# TIDA-010967_xWRL6432_Chip.net
KiCad netlist of a schematic drawn in Altium Designer
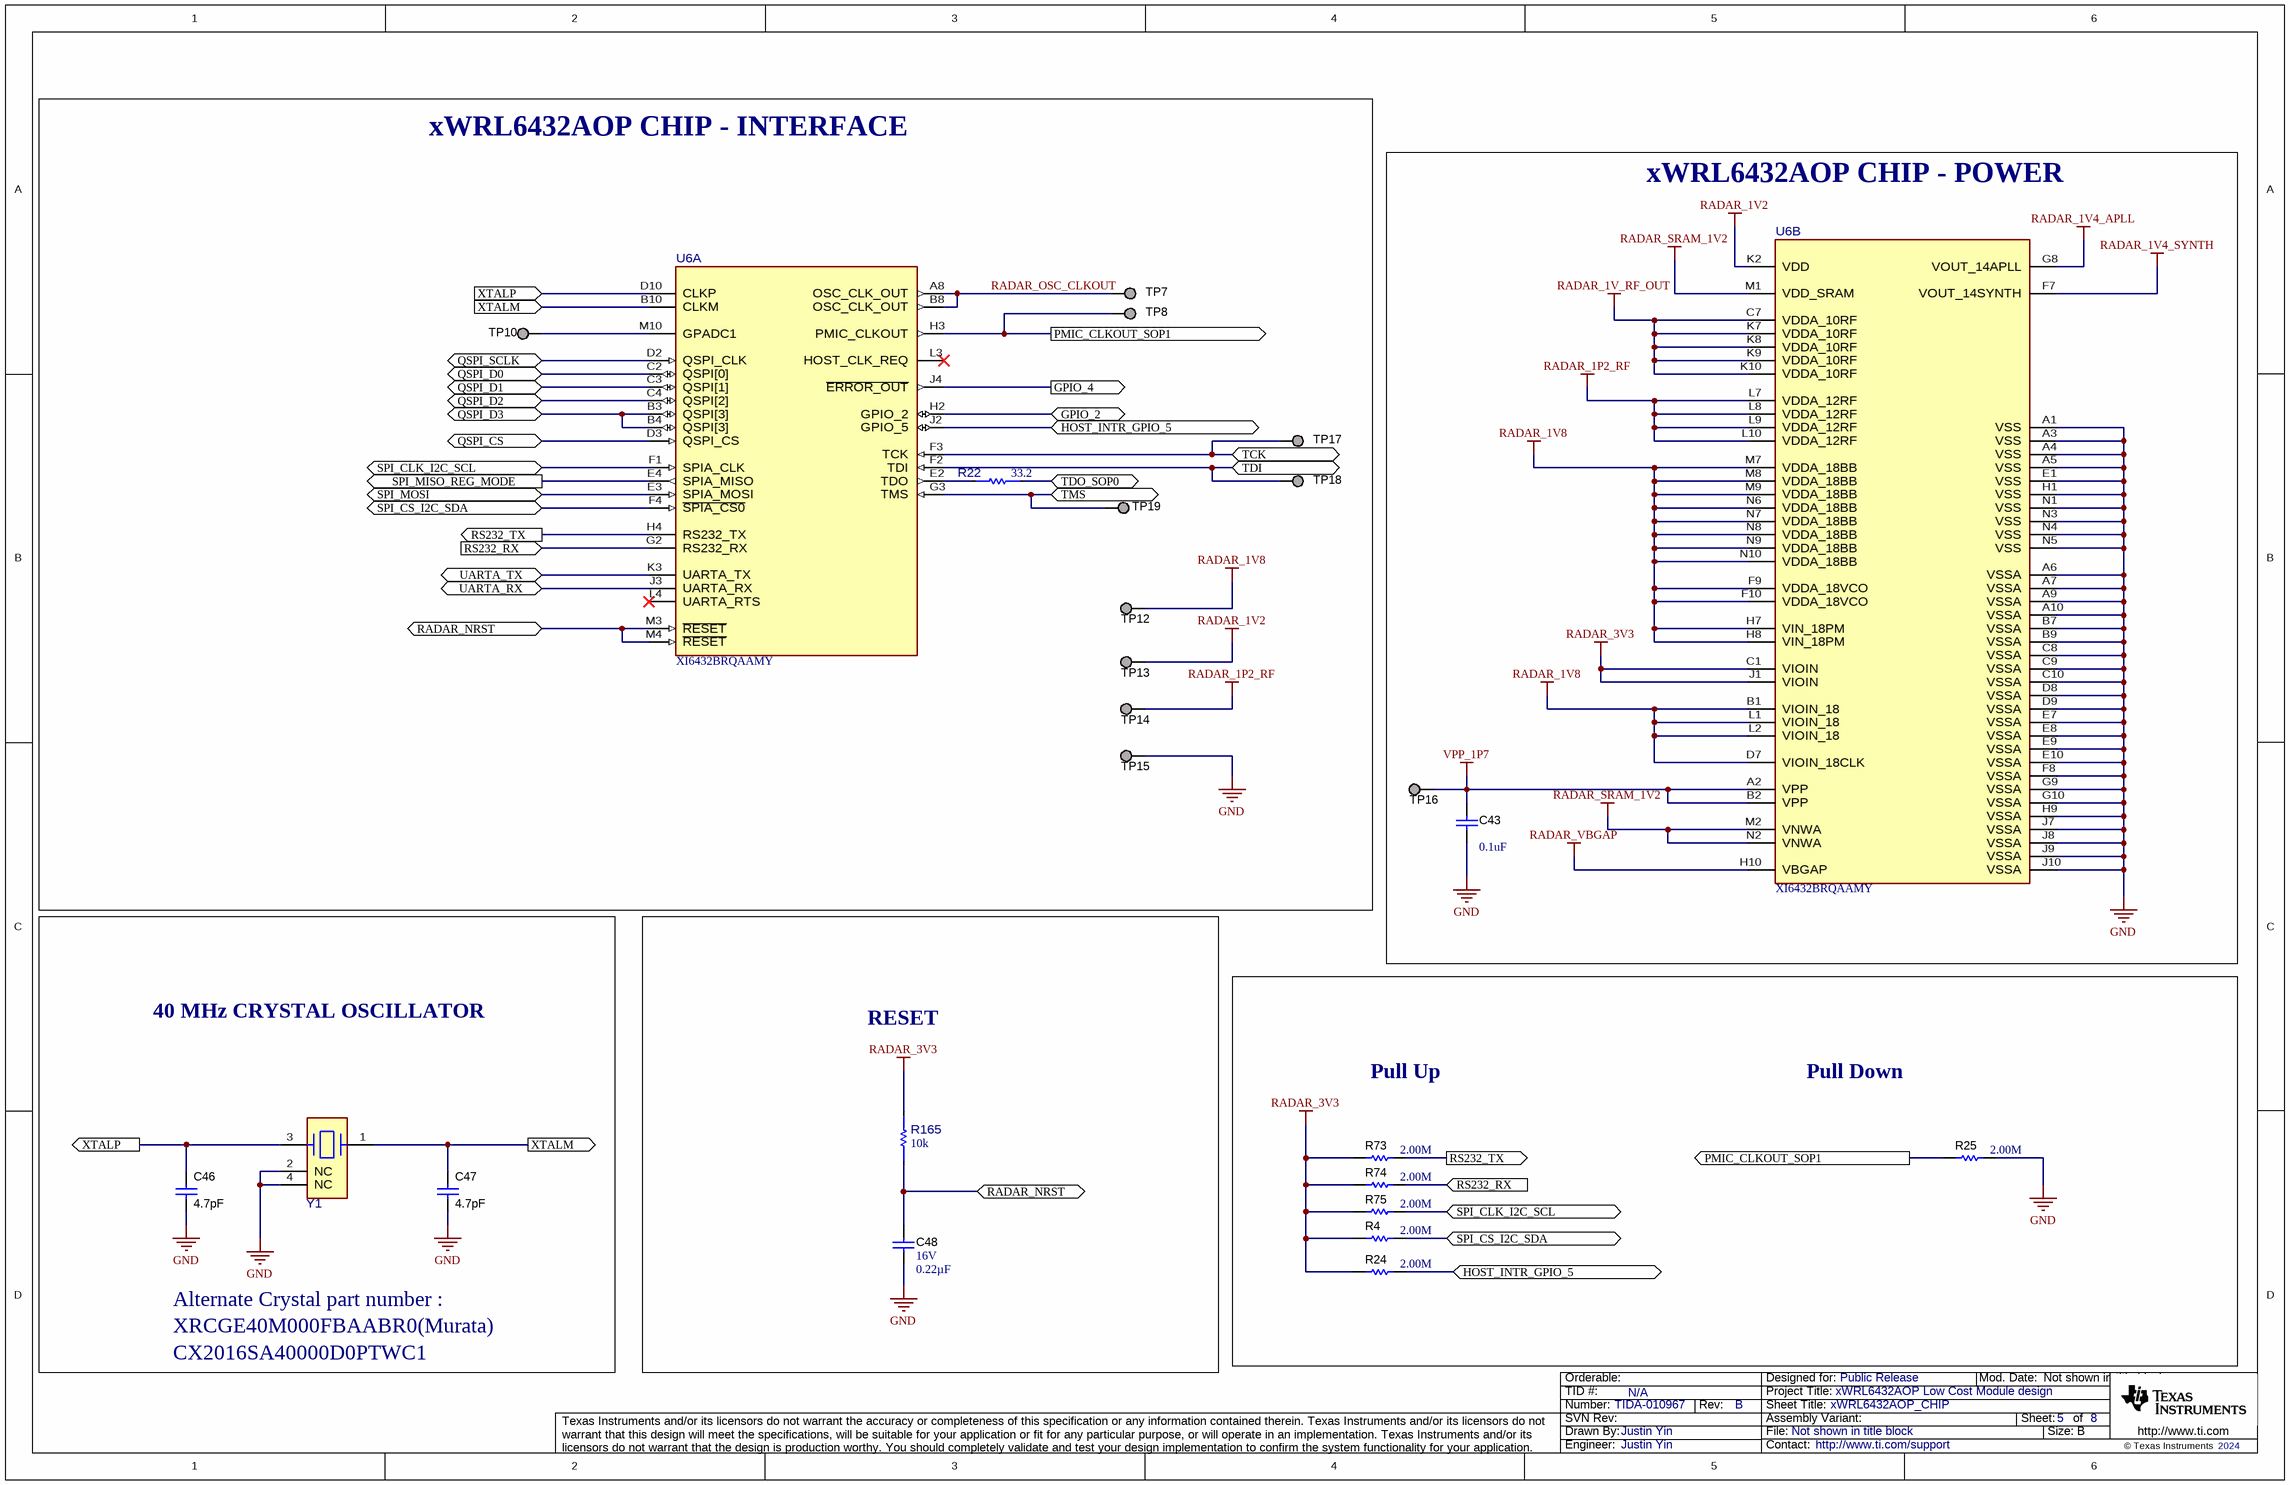
[diagram p0: TIDA-010967_xWRL6432_Chip.SchDoc]

(export (version "E")
  (design (tool "Eeschema 10.0.6"))
  (components
    (comp (ref "C43")
      (value "C1005X7R1H104K050BE")
      (footprint "0402")
      (description "CAP, CERM, 0.1 uF, 50 V,+/- 10%, X7R, 0402")
      (fields
        (field (name "MANUFACTURER") "TDK")
        (field (name "VALUEDISPLAYED") "0.1uF")
        (field (name "PUBLISHER") "Texas Instruments")
      )
      (libsource (lib "Altium Vault - TI") (part "Capacitor"))
    )
    (comp (ref "C46")
      (value "GJM1555C1H4R7BB01D")
      (footprint "0402L")
      (description "CAP, CERM, 4.7 pF, 50 V, +/- 2%, C0G/NP0, 0402")
      (fields
        (field (name "MANUFACTURER") "MuRata")
        (field (name "VALUEDISPLAYED") "4.7pF")
        (field (name "PUBLISHER") "Texas Instruments")
      )
      (libsource (lib "Altium Vault - TI") (part "CMP-0006367-2"))
    )
    (comp (ref "C47")
      (value "GJM1555C1H4R7BB01D")
      (footprint "0402L")
      (description "CAP, CERM, 4.7 pF, 50 V, +/- 2%, C0G/NP0, 0402")
      (fields
        (field (name "MANUFACTURER") "MuRata")
        (field (name "VALUEDISPLAYED") "4.7pF")
        (field (name "PUBLISHER") "Texas Instruments")
      )
      (libsource (lib "Altium Vault - TI") (part "CMP-0006367-2"))
    )
    (comp (ref "C48")
      (value "CL05B224KO5NNNC")
      (footprint "0402L")
      (description "CAP, CERM, 0.22 µF, 16 V,+/- 10%, X7R, 0402")
      (fields
        (field (name "MANUFACTURER") "Samsung Electro-Mechanics")
        (field (name "VDC_V") "16V")
        (field (name "VALUEDISPLAYED") "0.22µF")
      )
      (libsource (lib "Altium Vault - TI") (part "Capacitor"))
    )
    (comp (ref "R4")
      (value "CRCW04022M00FKED")
      (footprint "0402")
      (description "RES, 2.00 M, 1%, 0.063 W, AEC-Q200 Grade 0, 0402")
      (fields (field (name "MANUFACTURER") "Vishay-Dale") (field (name "VALUEDISPLAYED") "2.00M"))
      (libsource (lib "Altium Vault - TI") (part "Resistor"))
    )
    (comp (ref "R22")
      (value "33.2")
      (footprint "FP-RT0402FRE0733R2L_0402-MFG")
      (description "33.2 Ohms ±1% 0.063W, 1/16W Chip Resistor 0402 (1005 Metric) Thin Film")
      (fields (field (name "MANUFACTURER") "Yageo") (field (name "PARTNUMBER") "RT0402FRE0733R2L"))
      (libsource (lib "Altium Vault - TI") (part "SYM-RT0402FRE0733R2L"))
    )
    (comp (ref "R24")
      (value "CRCW04022M00FKED")
      (footprint "0402")
      (description "RES, 2.00 M, 1%, 0.063 W, AEC-Q200 Grade 0, 0402")
      (fields (field (name "MANUFACTURER") "Vishay-Dale") (field (name "VALUEDISPLAYED") "2.00M"))
      (libsource (lib "Altium Vault - TI") (part "Resistor"))
    )
    (comp (ref "R25")
      (value "CRCW04022M00FKED")
      (footprint "0402")
      (description "RES, 2.00 M, 1%, 0.063 W, AEC-Q200 Grade 0, 0402")
      (fields (field (name "MANUFACTURER") "Vishay-Dale") (field (name "VALUEDISPLAYED") "2.00M"))
      (libsource (lib "Altium Vault - TI") (part "Resistor"))
    )
    (comp (ref "R73")
      (value "CRCW04022M00FKED")
      (footprint "0402")
      (description "RES, 2.00 M, 1%, 0.063 W, AEC-Q200 Grade 0, 0402")
      (fields (field (name "MANUFACTURER") "Vishay-Dale") (field (name "VALUEDISPLAYED") "2.00M"))
      (libsource (lib "Altium Vault - TI") (part "Resistor"))
    )
    (comp (ref "R74")
      (value "CRCW04022M00FKED")
      (footprint "0402")
      (description "RES, 2.00 M, 1%, 0.063 W, AEC-Q200 Grade 0, 0402")
      (fields (field (name "MANUFACTURER") "Vishay-Dale") (field (name "VALUEDISPLAYED") "2.00M"))
      (libsource (lib "Altium Vault - TI") (part "Resistor"))
    )
    (comp (ref "R75")
      (value "CRCW04022M00FKED")
      (footprint "0402")
      (description "RES, 2.00 M, 1%, 0.063 W, AEC-Q200 Grade 0, 0402")
      (fields (field (name "MANUFACTURER") "Vishay-Dale") (field (name "VALUEDISPLAYED") "2.00M"))
      (libsource (lib "Altium Vault - TI") (part "Resistor"))
    )
    (comp (ref "R165")
      (value "ERJ-1RHD1002C")
      (footprint "FP-ERJ-1RHD1002C_0201-MFG")
      (description "Res Thick Film 0201 10K Ohm 0.5% 0.05W ±50ppm/°C Molded SMD Pressed Carrier T/R")
      (fields
        (field (name "MANUFACTURER") "Panasonic")
        (field (name "RES_OHM") "10k")
        (field (name "DIGIKEY PART NUMBER") "P15980CT-ND")
      )
      (libsource (lib "Altium Vault - TI") (part "SYM-ERJ-1RHD1002C"))
    )
    (comp (ref "TP7")
      (value "TESTPOINT")
      (footprint "TP_25MIL-SMT")
      (description "TEST POINT.  No entry in BOM.")
      (libsource (lib "Altium Vault - TI") (part "TESTPOINT"))
    )
    (comp (ref "TP8")
      (value "TESTPOINT")
      (footprint "TP_25MIL-SMT")
      (description "TEST POINT.  No entry in BOM.")
      (libsource (lib "Altium Vault - TI") (part "TESTPOINT"))
    )
    (comp (ref "TP10")
      (value "TESTPOINT")
      (footprint "TP_25MIL-SMT")
      (description "TEST POINT.  No entry in BOM.")
      (libsource (lib "Altium Vault - TI") (part "TESTPOINT"))
    )
    (comp (ref "TP12")
      (value "TESTPOINT")
      (footprint "TP_25MIL-SMT")
      (description "TEST POINT.  No entry in BOM.")
      (libsource (lib "Altium Vault - TI") (part "TESTPOINT"))
    )
    (comp (ref "TP13")
      (value "TESTPOINT")
      (footprint "TP_25MIL-SMT")
      (description "TEST POINT.  No entry in BOM.")
      (libsource (lib "Altium Vault - TI") (part "TESTPOINT"))
    )
    (comp (ref "TP14")
      (value "TESTPOINT")
      (footprint "TP_25MIL-SMT")
      (description "TEST POINT.  No entry in BOM.")
      (libsource (lib "Altium Vault - TI") (part "TESTPOINT"))
    )
    (comp (ref "TP15")
      (value "TESTPOINT")
      (footprint "TP_25MIL-SMT")
      (description "TEST POINT.  No entry in BOM.")
      (libsource (lib "Altium Vault - TI") (part "TESTPOINT"))
    )
    (comp (ref "TP16")
      (value "TESTPOINT")
      (footprint "TP_25MIL-SMT")
      (description "TEST POINT.  No entry in BOM.")
      (libsource (lib "Altium Vault - TI") (part "TESTPOINT"))
    )
    (comp (ref "TP17")
      (value "TESTPOINT")
      (footprint "TP_25MIL-SMT")
      (description "TEST POINT.  No entry in BOM.")
      (libsource (lib "Altium Vault - TI") (part "TESTPOINT"))
    )
    (comp (ref "TP18")
      (value "TESTPOINT")
      (footprint "TP_25MIL-SMT")
      (description "TEST POINT.  No entry in BOM.")
      (libsource (lib "Altium Vault - TI") (part "TESTPOINT"))
    )
    (comp (ref "TP19")
      (value "TESTPOINT")
      (footprint "TP_25MIL-SMT")
      (description "TEST POINT.  No entry in BOM.")
      (libsource (lib "Altium Vault - TI") (part "TESTPOINT"))
    )
    (comp (ref "U6")
      (value "XI6432BRQAAMY")
      (footprint "AMY0101A-MFG")
      (fields (field (name "MANUFACTURER") "Texas Instruments") (field (name "PARTNUMBER") "XI6432BRQAAMY"))
      (libsource (lib "Altium Vault - TI") (part "SYM-XWRL6432AoP"))
    )
    (comp (ref "Y1")
      (value "XRCGB40M000F1S2GR0")
      (footprint "FP-XRCGB40M000F1S2GR0_SMT_CRYSTAL_2MM0_1MM6-MFG")
      (description "Crystal Resonator 40MHz ±10ppm (Tol) ±20ppm (Stability) 8pF 50Ohm 4-Pin SMD T/R")
      (fields (field (name "MANUFACTURER") "Murata"))
      (libsource (lib "Altium Vault - TI") (part "SYM-XRCGB40M000F1S2GR0"))
    )
  )
  (nets
    (net (code "1") (name "/GPIO_2") (class "Default")
      (node (ref "U6") (pin "H2") (pinfunction "GPIO_2_H2") (pintype "bidirectional"))
    )
    (net (code "2") (name "/GPIO_4") (class "Default")
      (node (ref "U6") (pin "J4") (pinfunction "~{ERROR_OUT}_J4") (pintype "output"))
    )
    (net (code "3") (name "/HOST_INTR_GPIO_5") (class "Default")
      (node (ref "R24") (pin "2") (pinfunction "2_2") (pintype "passive"))
      (node (ref "U6") (pin "J2") (pinfunction "GPIO_5_J2") (pintype "bidirectional"))
    )
    (net (code "4") (name "/PMIC_CLKOUT_SOP1") (class "Default")
      (node (ref "R25") (pin "1") (pinfunction "1_1") (pintype "passive"))
      (node (ref "TP8") (pin "1") (pintype "passive"))
      (node (ref "U6") (pin "H3") (pinfunction "PMIC_CLKOUT_H3") (pintype "output"))
    )
    (net (code "5") (name "/QSPI_CS") (class "Default")
      (node (ref "U6") (pin "D3") (pinfunction "QSPI_CS_D3") (pintype "input"))
    )
    (net (code "6") (name "/QSPI_D0") (class "Default")
      (node (ref "U6") (pin "C2") (pinfunction "QSPI[0]_C2") (pintype "bidirectional"))
    )
    (net (code "7") (name "/QSPI_D1") (class "Default")
      (node (ref "U6") (pin "C3") (pinfunction "QSPI[1]_C3") (pintype "bidirectional"))
    )
    (net (code "8") (name "/QSPI_D2") (class "Default")
      (node (ref "U6") (pin "C4") (pinfunction "QSPI[2]_C4") (pintype "bidirectional"))
    )
    (net (code "9") (name "/QSPI_D3") (class "Default")
      (node (ref "U6") (pin "B3") (pinfunction "QSPI[3]_B3") (pintype "bidirectional"))
      (node (ref "U6") (pin "B4") (pinfunction "QSPI[3]_B4") (pintype "bidirectional"))
    )
    (net (code "10") (name "/QSPI_SCLK") (class "Default")
      (node (ref "U6") (pin "D2") (pinfunction "QSPI_CLK_D2") (pintype "input"))
    )
    (net (code "11") (name "/RADAR_NRST") (class "Default")
      (node (ref "C48") (pin "2") (pinfunction "2_2") (pintype "passive"))
      (node (ref "R165") (pin "1") (pinfunction "1_1") (pintype "passive"))
      (node (ref "U6") (pin "M3") (pinfunction "~{RESET}_M3") (pintype "input"))
      (node (ref "U6") (pin "M4") (pinfunction "~{RESET}_M4") (pintype "input"))
    )
    (net (code "12") (name "/RADAR_OSC_CLKOUT") (class "Default")
      (node (ref "TP7") (pin "1") (pintype "passive"))
      (node (ref "U6") (pin "A8") (pinfunction "OSC_CLK_OUT_A8") (pintype "output"))
      (node (ref "U6") (pin "B8") (pinfunction "OSC_CLK_OUT_B8") (pintype "output"))
    )
    (net (code "13") (name "/RS232_RX") (class "Default")
      (node (ref "R74") (pin "2") (pinfunction "2_2") (pintype "passive"))
      (node (ref "U6") (pin "G2") (pinfunction "RS232_RX_G2") (pintype "passive"))
    )
    (net (code "14") (name "/RS232_TX") (class "Default")
      (node (ref "R73") (pin "2") (pinfunction "2_2") (pintype "passive"))
      (node (ref "U6") (pin "H4") (pinfunction "RS232_TX_H4") (pintype "passive"))
    )
    (net (code "15") (name "/SPI_CLK_I2C_SCL") (class "Default")
      (node (ref "R75") (pin "2") (pinfunction "2_2") (pintype "passive"))
      (node (ref "U6") (pin "F1") (pinfunction "SPIA_CLK_F1") (pintype "input"))
    )
    (net (code "16") (name "/SPI_CS_I2C_SDA") (class "Default")
      (node (ref "R4") (pin "2") (pinfunction "2_2") (pintype "passive"))
      (node (ref "U6") (pin "F4") (pinfunction "~{SPIA_CS0}_F4") (pintype "input"))
    )
    (net (code "17") (name "/SPI_MISO_REG_MODE") (class "Default")
      (node (ref "U6") (pin "E4") (pinfunction "SPIA_MISO_E4") (pintype "output"))
    )
    (net (code "18") (name "/SPI_MOSI") (class "Default")
      (node (ref "U6") (pin "E3") (pinfunction "SPIA_MOSI_E3") (pintype "input"))
    )
    (net (code "19") (name "/TCK") (class "Default")
      (node (ref "TP17") (pin "1") (pintype "passive"))
      (node (ref "U6") (pin "F3") (pinfunction "TCK_F3") (pintype "input"))
    )
    (net (code "20") (name "/TDI") (class "Default")
      (node (ref "TP18") (pin "1") (pintype "passive"))
      (node (ref "U6") (pin "F2") (pinfunction "TDI_F2") (pintype "input"))
    )
    (net (code "21") (name "/TDO_SOP0") (class "Default")
      (node (ref "R22") (pin "1") (pinfunction "1_1") (pintype "passive"))
    )
    (net (code "22") (name "/TMS") (class "Default")
      (node (ref "TP19") (pin "1") (pintype "passive"))
      (node (ref "U6") (pin "G3") (pinfunction "TMS_G3") (pintype "input"))
    )
    (net (code "23") (name "/UARTA_RX") (class "Default")
      (node (ref "U6") (pin "J3") (pinfunction "UARTA_RX_J3") (pintype "passive"))
    )
    (net (code "24") (name "/UARTA_TX") (class "Default")
      (node (ref "U6") (pin "K3") (pinfunction "UARTA_TX_K3") (pintype "passive"))
    )
    (net (code "25") (name "/XTALM") (class "Default")
      (node (ref "C47") (pin "2") (pinfunction "2_2") (pintype "passive"))
      (node (ref "U6") (pin "B10") (pinfunction "CLKM_B10") (pintype "passive"))
      (node (ref "Y1") (pin "1") (pinfunction "1_1") (pintype "passive"))
    )
    (net (code "26") (name "/XTALP") (class "Default")
      (node (ref "C46") (pin "2") (pinfunction "2_2") (pintype "passive"))
      (node (ref "U6") (pin "D10") (pinfunction "CLKP_D10") (pintype "passive"))
      (node (ref "Y1") (pin "3") (pinfunction "3_3") (pintype "passive"))
    )
    (net (code "27") (name "GND") (class "Default")
      (node (ref "C43") (pin "2") (pinfunction "2_2") (pintype "passive"))
      (node (ref "C46") (pin "1") (pinfunction "1_1") (pintype "passive"))
      (node (ref "C47") (pin "1") (pinfunction "1_1") (pintype "passive"))
      (node (ref "C48") (pin "1") (pinfunction "1_1") (pintype "passive"))
      (node (ref "R25") (pin "2") (pinfunction "2_2") (pintype "passive"))
      (node (ref "TP15") (pin "1") (pintype "passive"))
      (node (ref "U6") (pin "A1") (pinfunction "VSS_A1") (pintype "power_in"))
      (node (ref "U6") (pin "A10") (pinfunction "VSSA_A10") (pintype "power_in"))
      (node (ref "U6") (pin "A3") (pinfunction "VSS_A3") (pintype "power_in"))
      (node (ref "U6") (pin "A4") (pinfunction "VSS_A4") (pintype "power_in"))
      (node (ref "U6") (pin "A5") (pinfunction "VSS_A5") (pintype "power_in"))
      (node (ref "U6") (pin "A6") (pinfunction "VSSA_A6") (pintype "power_in"))
      (node (ref "U6") (pin "A7") (pinfunction "VSSA_A7") (pintype "power_in"))
      (node (ref "U6") (pin "A9") (pinfunction "VSSA_A9") (pintype "power_in"))
      (node (ref "U6") (pin "B7") (pinfunction "VSSA_B7") (pintype "power_in"))
      (node (ref "U6") (pin "B9") (pinfunction "VSSA_B9") (pintype "power_in"))
      (node (ref "U6") (pin "C10") (pinfunction "VSSA_C10") (pintype "power_in"))
      (node (ref "U6") (pin "C8") (pinfunction "VSSA_C8") (pintype "power_in"))
      (node (ref "U6") (pin "C9") (pinfunction "VSSA_C9") (pintype "power_in"))
      (node (ref "U6") (pin "D8") (pinfunction "VSSA_D8") (pintype "power_in"))
      (node (ref "U6") (pin "D9") (pinfunction "VSSA_D9") (pintype "power_in"))
      (node (ref "U6") (pin "E1") (pinfunction "VSS_E1") (pintype "power_in"))
      (node (ref "U6") (pin "E10") (pinfunction "VSSA_E10") (pintype "power_in"))
      (node (ref "U6") (pin "E7") (pinfunction "VSSA_E7") (pintype "power_in"))
      (node (ref "U6") (pin "E8") (pinfunction "VSSA_E8") (pintype "power_in"))
      (node (ref "U6") (pin "E9") (pinfunction "VSSA_E9") (pintype "power_in"))
      (node (ref "U6") (pin "F8") (pinfunction "VSSA_F8") (pintype "power_in"))
      (node (ref "U6") (pin "G10") (pinfunction "VSSA_G10") (pintype "power_in"))
      (node (ref "U6") (pin "G9") (pinfunction "VSSA_G9") (pintype "power_in"))
      (node (ref "U6") (pin "H1") (pinfunction "VSS_H1") (pintype "power_in"))
      (node (ref "U6") (pin "H9") (pinfunction "VSSA_H9") (pintype "power_in"))
      (node (ref "U6") (pin "J10") (pinfunction "VSSA_J10") (pintype "power_in"))
      (node (ref "U6") (pin "J7") (pinfunction "VSSA_J7") (pintype "power_in"))
      (node (ref "U6") (pin "J8") (pinfunction "VSSA_J8") (pintype "power_in"))
      (node (ref "U6") (pin "J9") (pinfunction "VSSA_J9") (pintype "power_in"))
      (node (ref "U6") (pin "N1") (pinfunction "VSS_N1") (pintype "power_in"))
      (node (ref "U6") (pin "N3") (pinfunction "VSS_N3") (pintype "power_in"))
      (node (ref "U6") (pin "N4") (pinfunction "VSS_N4") (pintype "power_in"))
      (node (ref "U6") (pin "N5") (pinfunction "VSS_N5") (pintype "power_in"))
      (node (ref "Y1") (pin "2") (pinfunction "NC_2") (pintype "passive"))
      (node (ref "Y1") (pin "4") (pinfunction "NC_4") (pintype "passive"))
    )
    (net (code "28") (name "Net-(U6A-GPADC1)") (class "Default")
      (node (ref "TP10") (pin "1") (pintype "passive"))
      (node (ref "U6") (pin "M10") (pinfunction "GPADC1_M10") (pintype "passive"))
    )
    (net (code "29") (name "Net-(U6A-TDO)") (class "Default")
      (node (ref "R22") (pin "2") (pinfunction "2_2") (pintype "passive"))
      (node (ref "U6") (pin "E2") (pinfunction "TDO_E2") (pintype "output"))
    )
    (net (code "30") (name "RADAR_1P2_RF") (class "Default")
      (node (ref "TP14") (pin "1") (pintype "passive"))
      (node (ref "U6") (pin "L10") (pinfunction "VDDA_12RF_L10") (pintype "power_in"))
      (node (ref "U6") (pin "L7") (pinfunction "VDDA_12RF_L7") (pintype "power_in"))
      (node (ref "U6") (pin "L8") (pinfunction "VDDA_12RF_L8") (pintype "power_in"))
      (node (ref "U6") (pin "L9") (pinfunction "VDDA_12RF_L9") (pintype "power_in"))
    )
    (net (code "31") (name "RADAR_1V2") (class "Default")
      (node (ref "TP13") (pin "1") (pintype "passive"))
      (node (ref "U6") (pin "K2") (pinfunction "VDD_K2") (pintype "power_in"))
    )
    (net (code "32") (name "RADAR_1V4_APLL") (class "Default")
      (node (ref "U6") (pin "G8") (pinfunction "VOUT_14APLL_G8") (pintype "power_in"))
    )
    (net (code "33") (name "RADAR_1V4_SYNTH") (class "Default")
      (node (ref "U6") (pin "F7") (pinfunction "VOUT_14SYNTH_F7") (pintype "power_in"))
    )
    (net (code "34") (name "RADAR_1V8") (class "Default")
      (node (ref "TP12") (pin "1") (pintype "passive"))
      (node (ref "U6") (pin "B1") (pinfunction "VIOIN_18_B1") (pintype "power_in"))
      (node (ref "U6") (pin "D7") (pinfunction "VIOIN_18CLK_D7") (pintype "power_in"))
      (node (ref "U6") (pin "F10") (pinfunction "VDDA_18VCO_F10") (pintype "power_in"))
      (node (ref "U6") (pin "F9") (pinfunction "VDDA_18VCO_F9") (pintype "power_in"))
      (node (ref "U6") (pin "H7") (pinfunction "VIN_18PM_H7") (pintype "power_in"))
      (node (ref "U6") (pin "H8") (pinfunction "VIN_18PM_H8") (pintype "power_in"))
      (node (ref "U6") (pin "L1") (pinfunction "VIOIN_18_L1") (pintype "power_in"))
      (node (ref "U6") (pin "L2") (pinfunction "VIOIN_18_L2") (pintype "power_in"))
      (node (ref "U6") (pin "M7") (pinfunction "VDDA_18BB_M7") (pintype "power_in"))
      (node (ref "U6") (pin "M8") (pinfunction "VDDA_18BB_M8") (pintype "power_in"))
      (node (ref "U6") (pin "M9") (pinfunction "VDDA_18BB_M9") (pintype "power_in"))
      (node (ref "U6") (pin "N10") (pinfunction "VDDA_18BB_N10") (pintype "power_in"))
      (node (ref "U6") (pin "N6") (pinfunction "VDDA_18BB_N6") (pintype "power_in"))
      (node (ref "U6") (pin "N7") (pinfunction "VDDA_18BB_N7") (pintype "power_in"))
      (node (ref "U6") (pin "N8") (pinfunction "VDDA_18BB_N8") (pintype "power_in"))
      (node (ref "U6") (pin "N9") (pinfunction "VDDA_18BB_N9") (pintype "power_in"))
    )
    (net (code "35") (name "RADAR_1V_RF_OUT") (class "Default")
      (node (ref "U6") (pin "C7") (pinfunction "VDDA_10RF_C7") (pintype "power_in"))
      (node (ref "U6") (pin "K10") (pinfunction "VDDA_10RF_K10") (pintype "power_in"))
      (node (ref "U6") (pin "K7") (pinfunction "VDDA_10RF_K7") (pintype "power_in"))
      (node (ref "U6") (pin "K8") (pinfunction "VDDA_10RF_K8") (pintype "power_in"))
      (node (ref "U6") (pin "K9") (pinfunction "VDDA_10RF_K9") (pintype "power_in"))
    )
    (net (code "36") (name "RADAR_3V3") (class "Default")
      (node (ref "R165") (pin "2") (pinfunction "2_2") (pintype "passive"))
      (node (ref "R24") (pin "1") (pinfunction "1_1") (pintype "passive"))
      (node (ref "R4") (pin "1") (pinfunction "1_1") (pintype "passive"))
      (node (ref "R73") (pin "1") (pinfunction "1_1") (pintype "passive"))
      (node (ref "R74") (pin "1") (pinfunction "1_1") (pintype "passive"))
      (node (ref "R75") (pin "1") (pinfunction "1_1") (pintype "passive"))
      (node (ref "U6") (pin "C1") (pinfunction "VIOIN_C1") (pintype "power_in"))
      (node (ref "U6") (pin "J1") (pinfunction "VIOIN_J1") (pintype "power_in"))
    )
    (net (code "37") (name "RADAR_SRAM_1V2") (class "Default")
      (node (ref "U6") (pin "M1") (pinfunction "VDD_SRAM_M1") (pintype "power_in"))
      (node (ref "U6") (pin "M2") (pinfunction "VNWA_M2") (pintype "power_in"))
      (node (ref "U6") (pin "N2") (pinfunction "VNWA_N2") (pintype "power_in"))
    )
    (net (code "38") (name "RADAR_VBGAP") (class "Default")
      (node (ref "U6") (pin "H10") (pinfunction "VBGAP_H10") (pintype "power_in"))
    )
    (net (code "39") (name "VPP_1P7") (class "Default")
      (node (ref "C43") (pin "1") (pinfunction "1_1") (pintype "passive"))
      (node (ref "TP16") (pin "1") (pintype "passive"))
      (node (ref "U6") (pin "A2") (pinfunction "VPP_A2") (pintype "power_in"))
      (node (ref "U6") (pin "B2") (pinfunction "VPP_B2") (pintype "power_in"))
    )
    (net (code "40") (name "unconnected-(U6A-HOST_CLK_REQ-PadL3)") (class "Default")
      (node (ref "U6") (pin "L3") (pinfunction "HOST_CLK_REQ_L3") (pintype "passive+no_connect"))
    )
    (net (code "41") (name "unconnected-(U6A-UARTA_RTS-PadL4)") (class "Default")
      (node (ref "U6") (pin "L4") (pinfunction "UARTA_RTS_L4") (pintype "passive+no_connect"))
    )
  )
)
